# ESP32_layout.net
KiCad netlist of a schematic drawn in EasyEDA
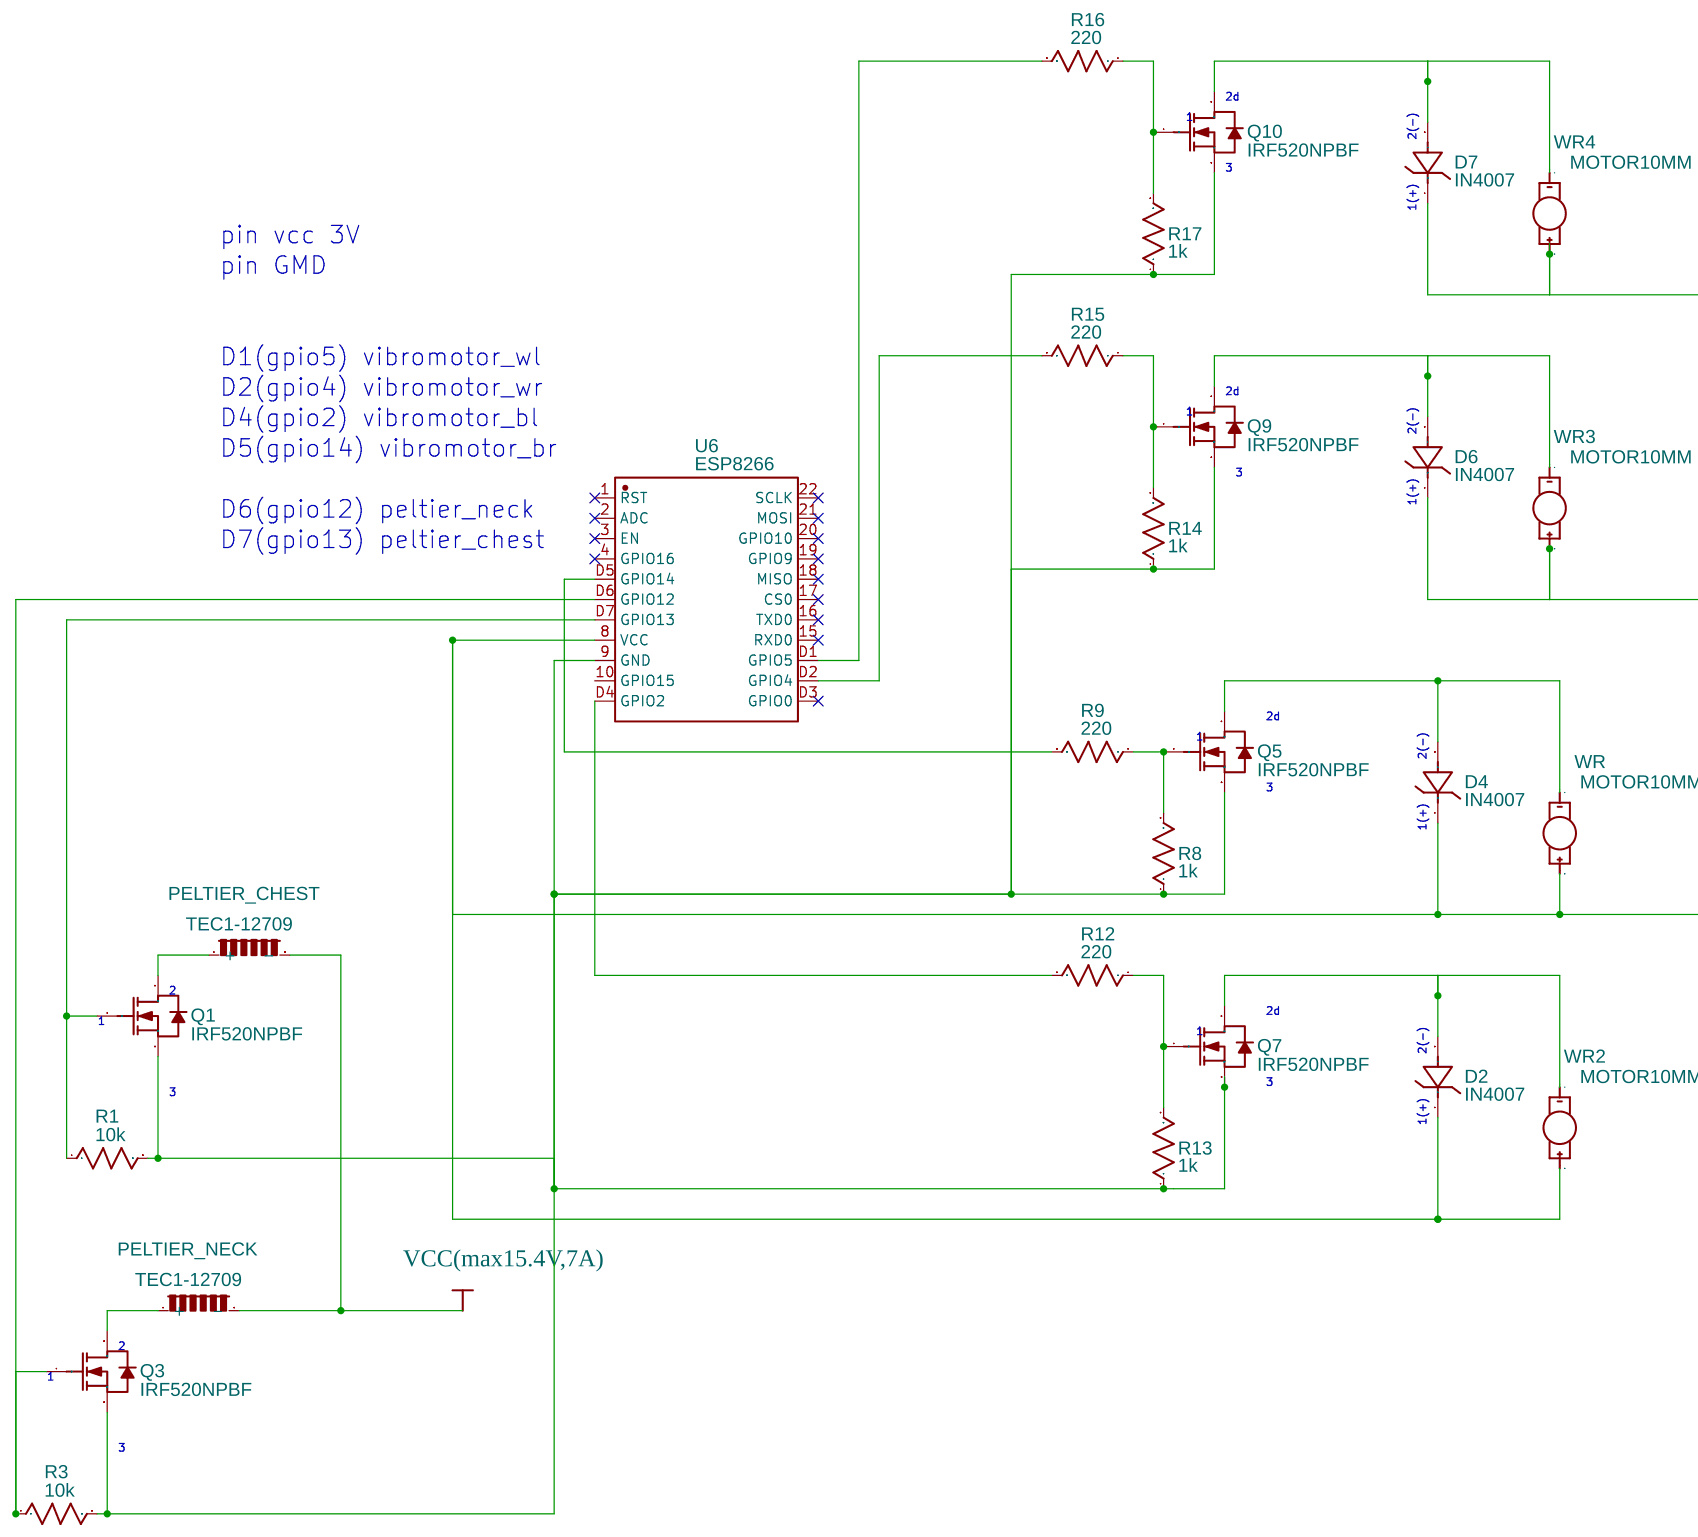
[diagram p0: schema_proto2]
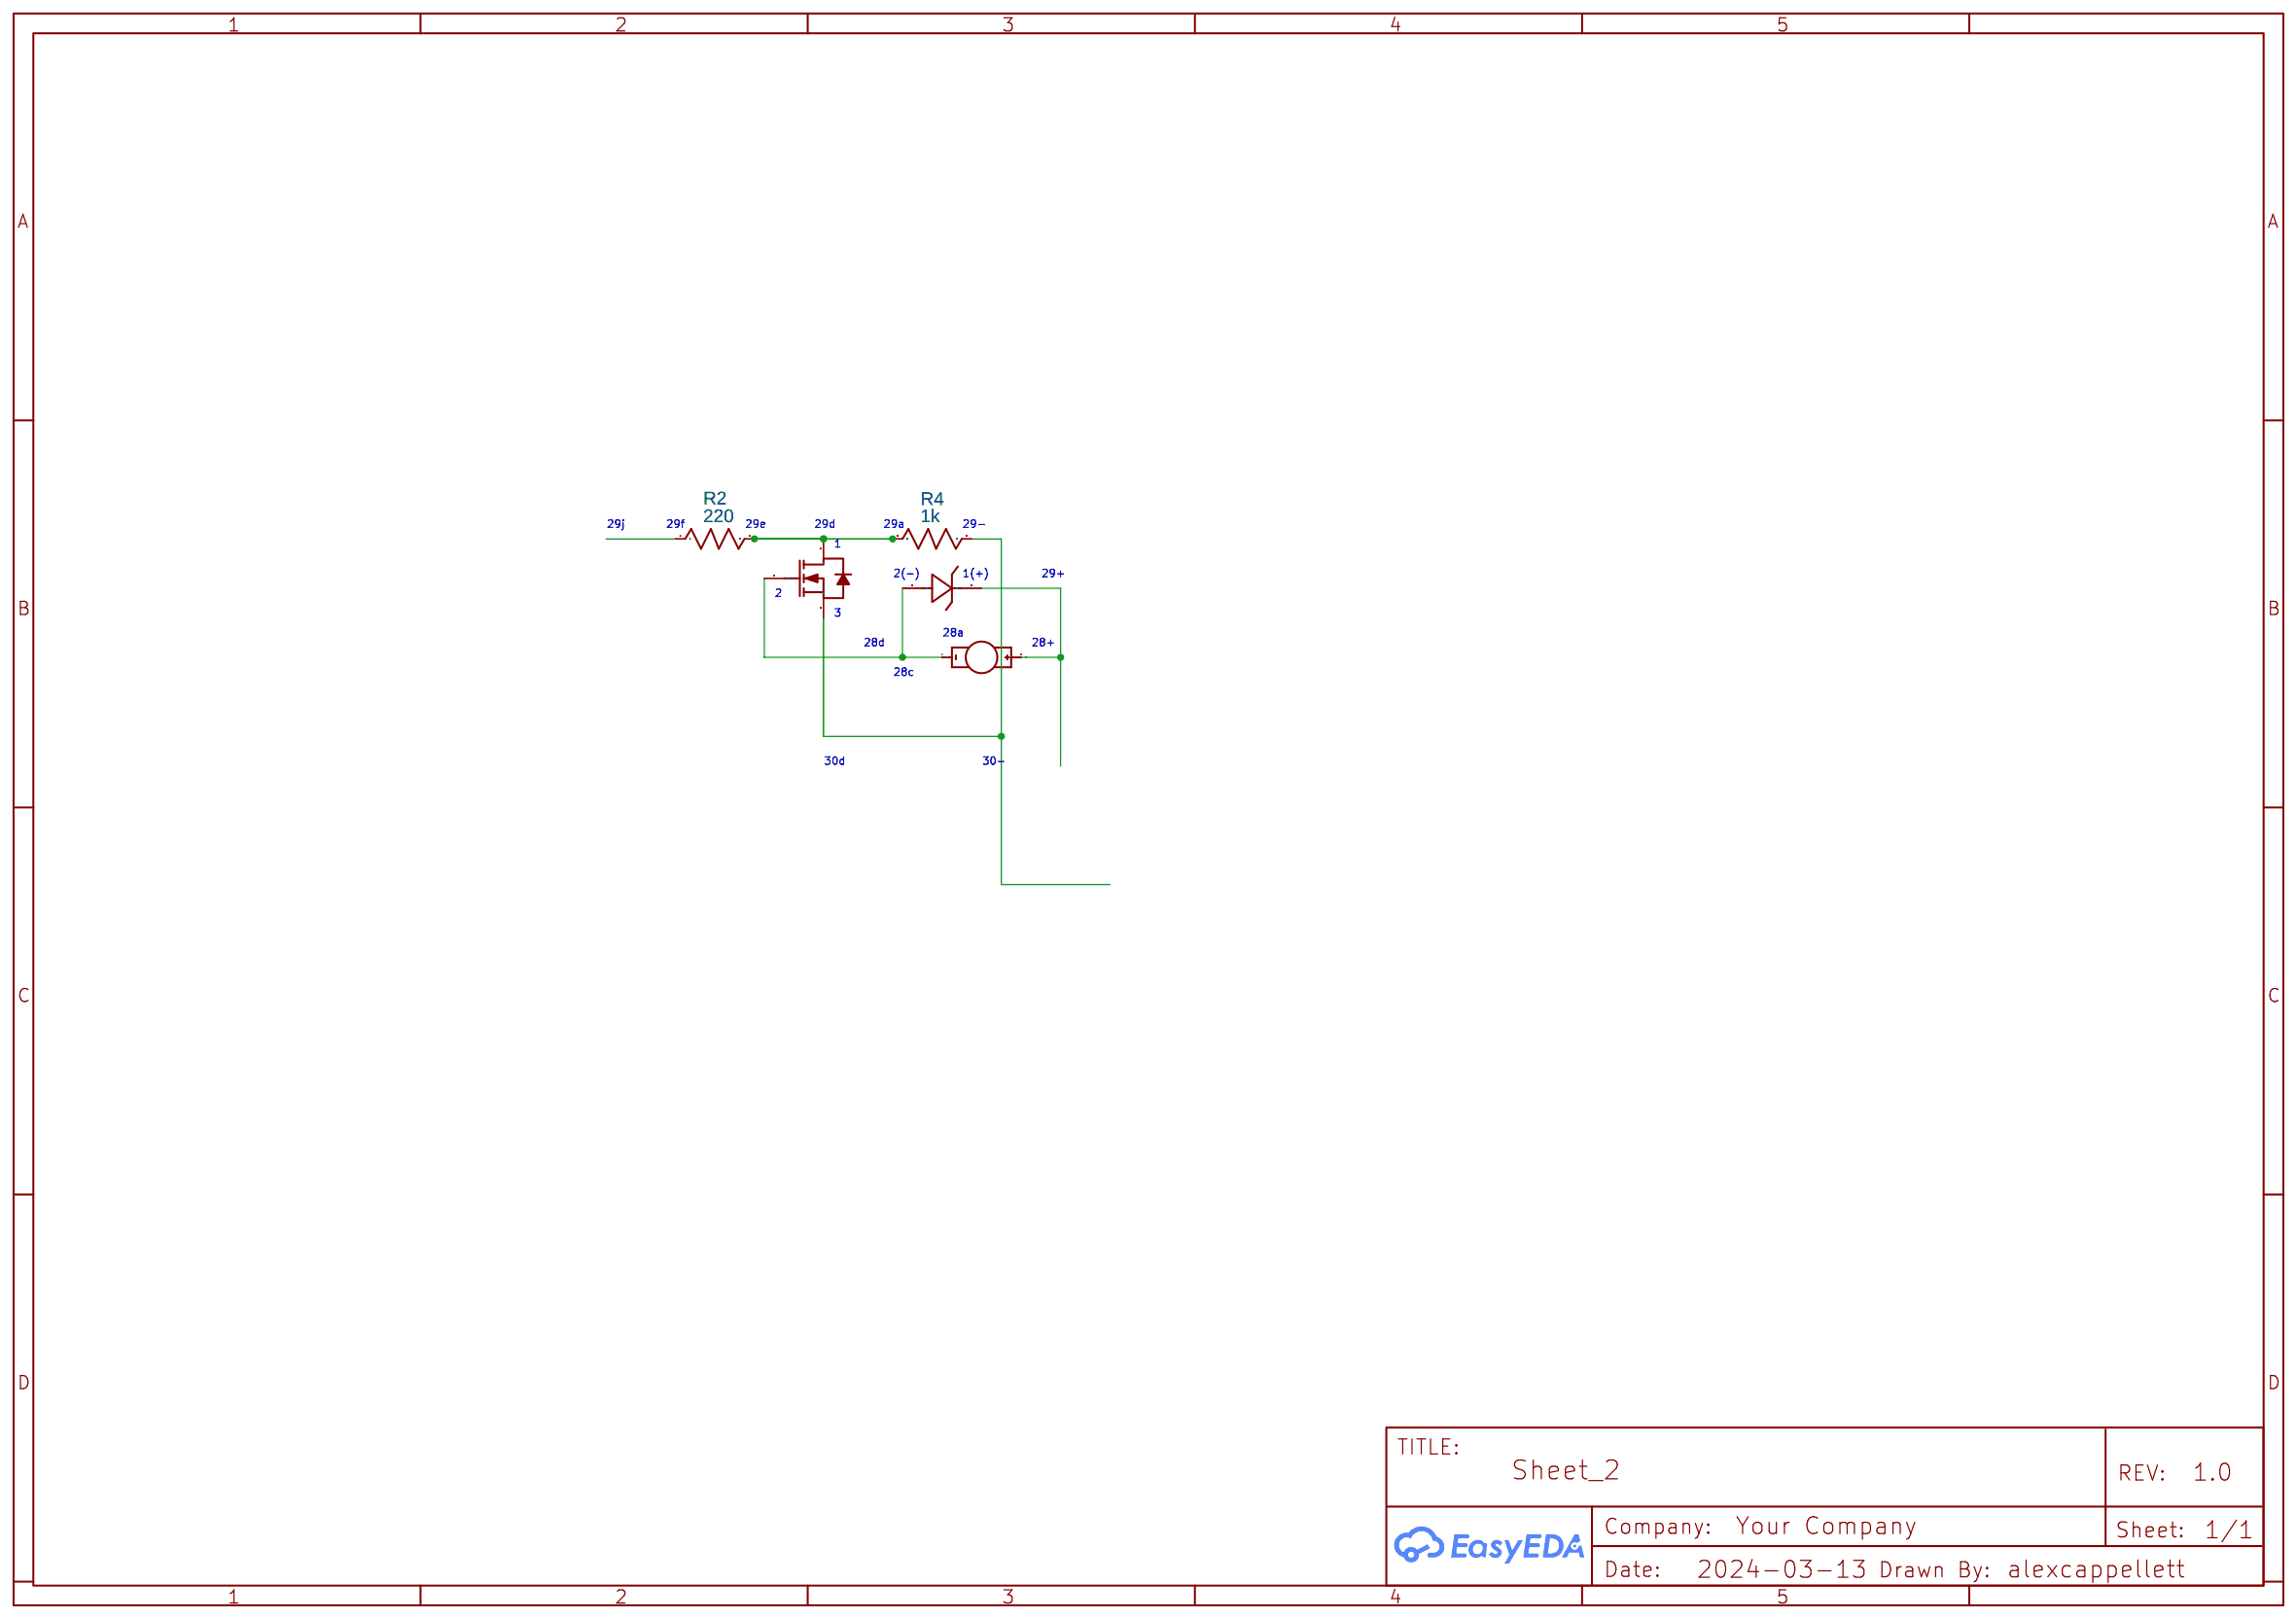
[diagram p1: schema_motor_details]
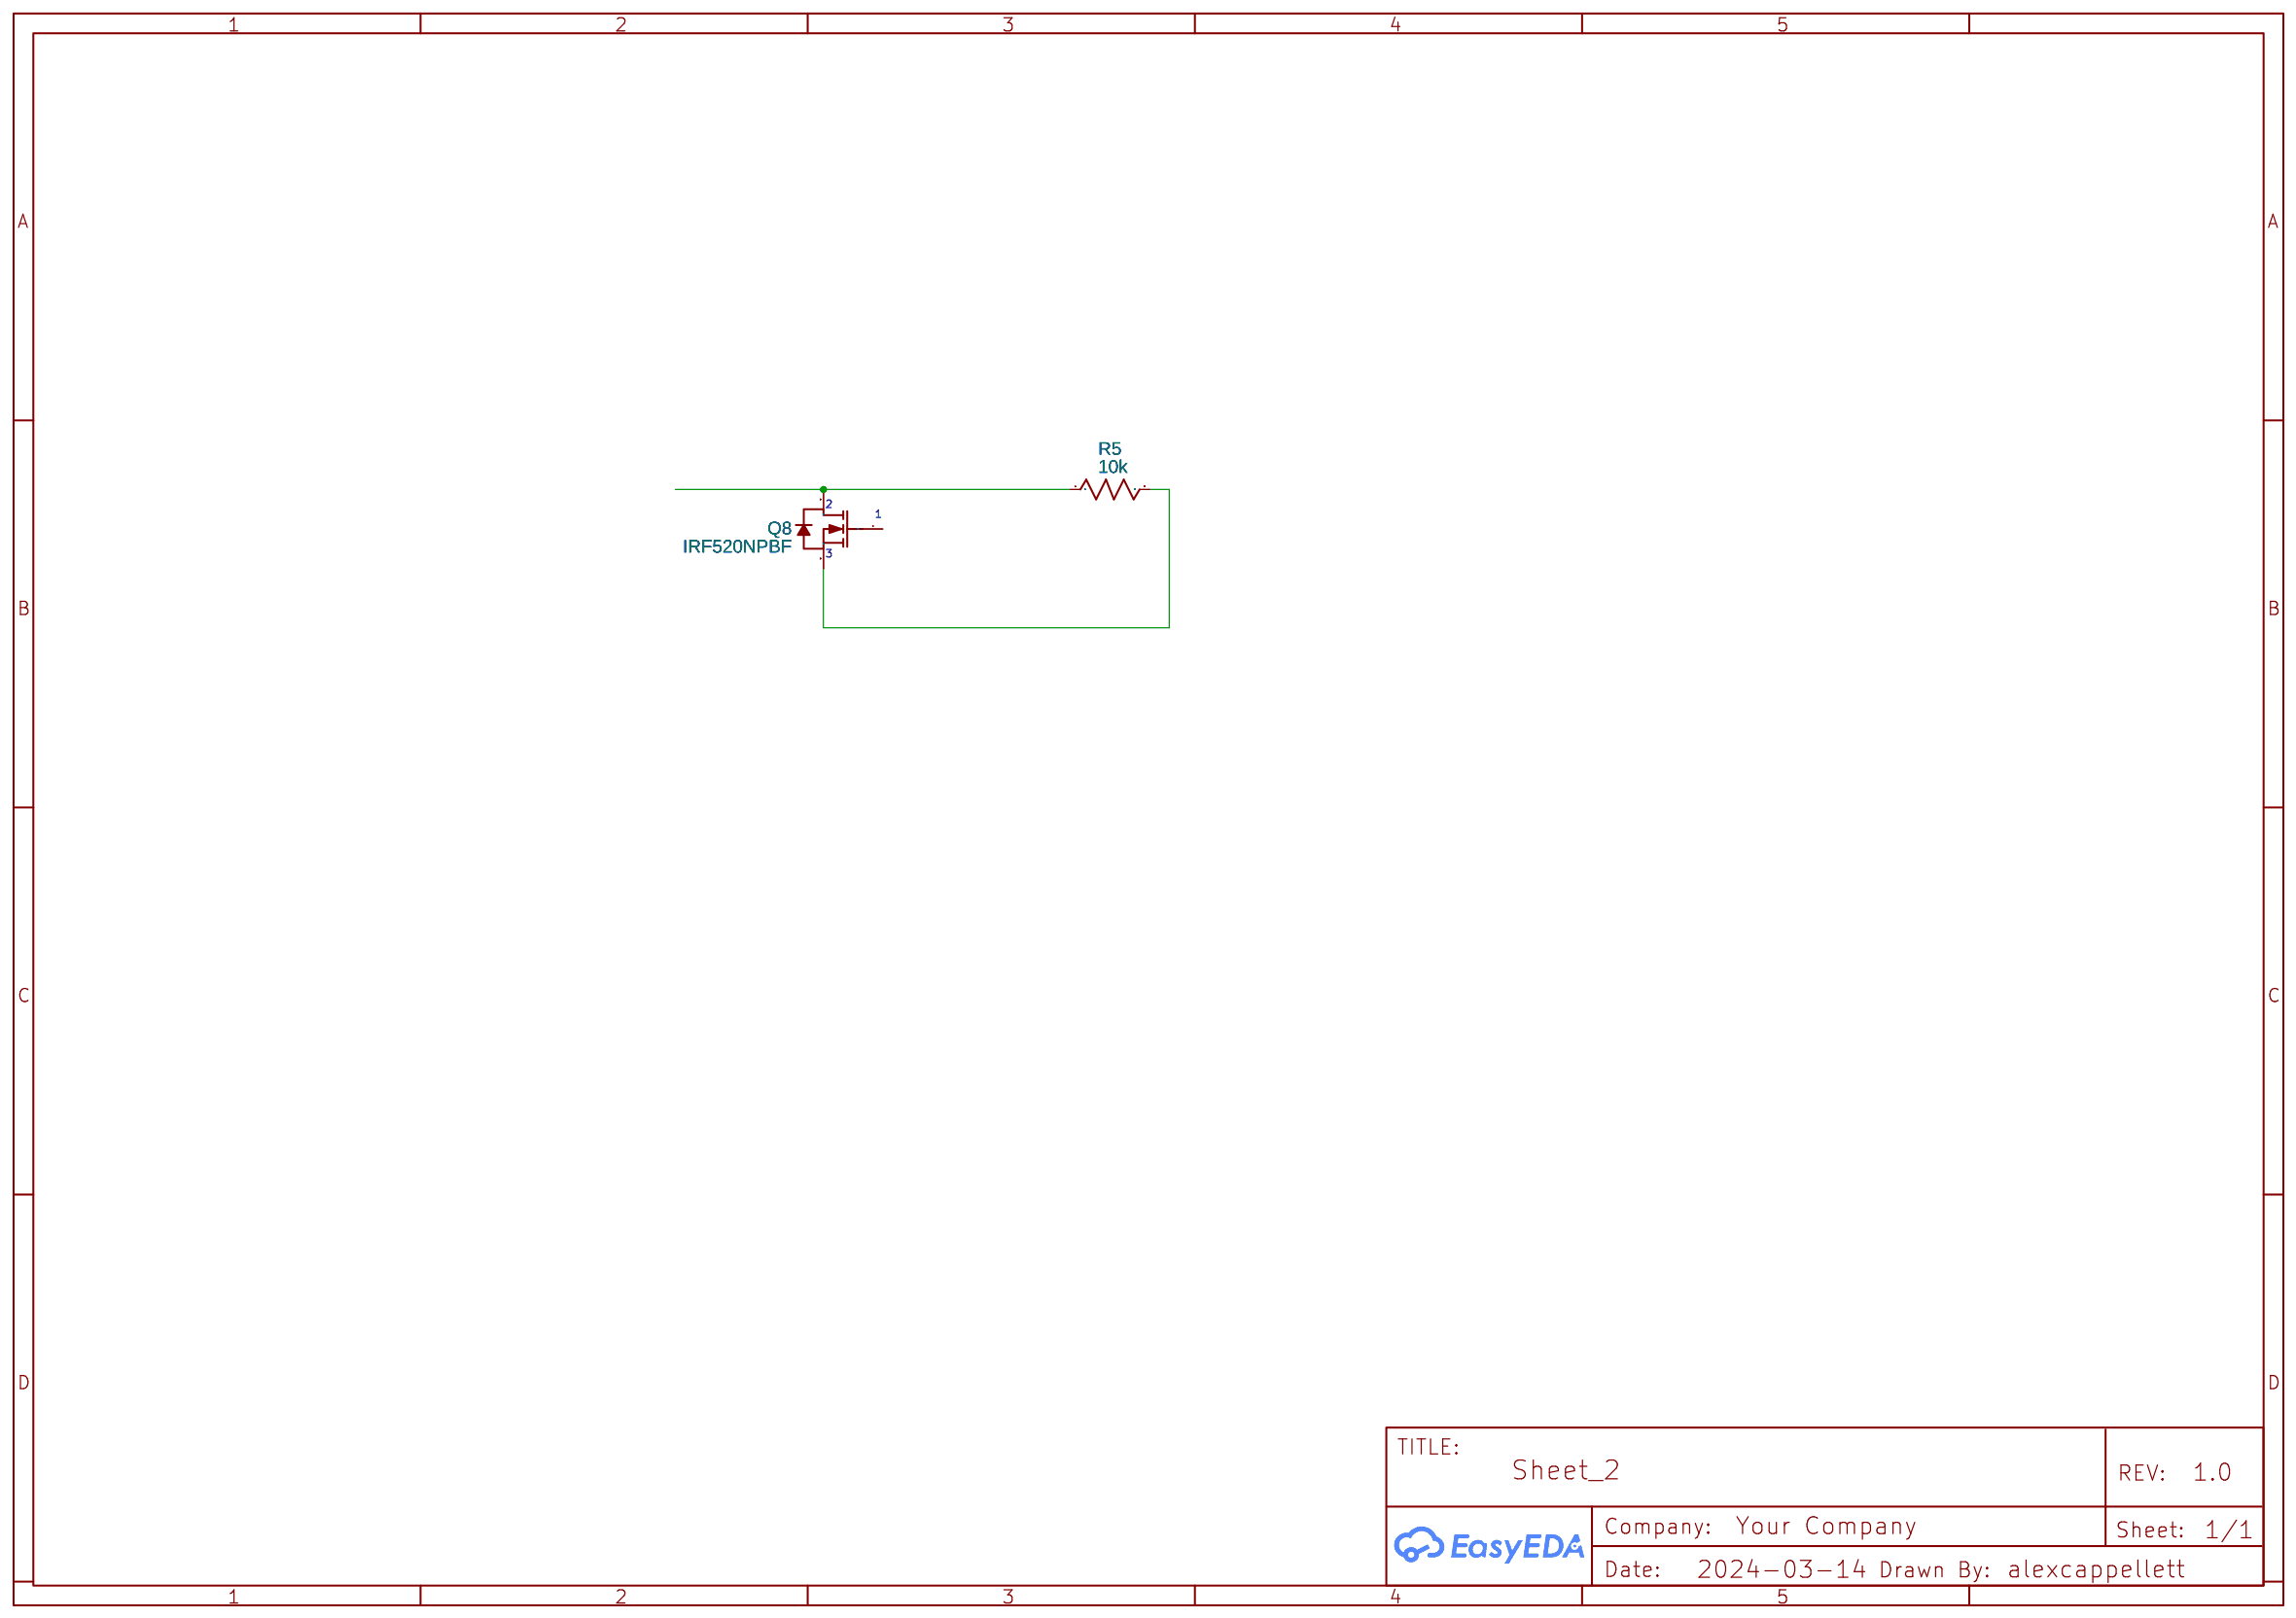
[diagram p2: Sheet_2]

(export (version "E")
  (design (tool "Eeschema 10.0.6"))
  (components
    (comp (ref "D2") (value "IN4007") (libsource (lib "") (part "IN4007")))
    (comp (ref "D4") (value "IN4007") (libsource (lib "") (part "IN4007")))
    (comp (ref "D6") (value "IN4007") (libsource (lib "") (part "IN4007")))
    (comp (ref "D7") (value "IN4007") (libsource (lib "") (part "IN4007")))
    (comp (ref "PELTIER_CHEST") (value "TEC1-12709") (libsource (lib "") (part "Peltier_Element_1")))
    (comp (ref "PELTIER_NECK") (value "TEC1-12709") (libsource (lib "") (part "Peltier_Element")))
    (comp (ref "Q1")
      (value "IRF520NPBF")
      (fields (field (name "Manufacturer") "Infineon(英飞凌)"))
      (libsource (lib "") (part "IRF520NPBF"))
    )
    (comp (ref "Q3")
      (value "IRF520NPBF")
      (fields (field (name "Manufacturer") "Infineon(英飞凌)"))
      (libsource (lib "") (part "IRF520NPBF"))
    )
    (comp (ref "Q5")
      (value "IRF520NPBF")
      (fields (field (name "Manufacturer") "Infineon(英飞凌)"))
      (libsource (lib "") (part "IRF520NPBF"))
    )
    (comp (ref "Q7")
      (value "IRF520NPBF")
      (fields (field (name "Manufacturer") "Infineon(英飞凌)"))
      (libsource (lib "") (part "IRF520NPBF"))
    )
    (comp (ref "Q9")
      (value "IRF520NPBF")
      (fields (field (name "Manufacturer") "Infineon(英飞凌)"))
      (libsource (lib "") (part "IRF520NPBF"))
    )
    (comp (ref "Q10")
      (value "IRF520NPBF")
      (fields (field (name "Manufacturer") "Infineon(英飞凌)"))
      (libsource (lib "") (part "IRF520NPBF"))
    )
    (comp (ref "R1") (value "10k") (libsource (lib "") (part "R_0603_US_1")))
    (comp (ref "R3") (value "10k") (libsource (lib "") (part "R_0603_US_1")))
    (comp (ref "R8") (value "1k") (libsource (lib "") (part "R_0603_US")))
    (comp (ref "R9") (value "220") (libsource (lib "") (part "R_0603_US_2")))
    (comp (ref "R12") (value "220") (libsource (lib "") (part "R_0603_US_2")))
    (comp (ref "R13") (value "1k") (libsource (lib "") (part "R_0603_US")))
    (comp (ref "R14") (value "1k") (libsource (lib "") (part "R_0603_US")))
    (comp (ref "R15") (value "220") (libsource (lib "") (part "R_0603_US_2")))
    (comp (ref "R16") (value "220") (libsource (lib "") (part "R_0603_US_2")))
    (comp (ref "R17") (value "1k") (libsource (lib "") (part "R_0603_US")))
    (comp (ref "U6") (value "ESP8266") (libsource (lib "") (part "ESP8266")))
    (comp (ref "WR") (value "MOTOR10MM") (libsource (lib "") (part "MOTOR10MM")))
    (comp (ref "WR2") (value "MOTOR10MM") (libsource (lib "") (part "MOTOR10MM")))
    (comp (ref "WR3") (value "MOTOR10MM") (libsource (lib "") (part "MOTOR10MM")))
    (comp (ref "WR4") (value "MOTOR10MM") (libsource (lib "") (part "MOTOR10MM")))
    (comp (ref "D1") (value "IN4007") (libsource (lib "") (part "IN4007")))
    (comp (ref "Q2")
      (value "IRF520NPBF")
      (fields (field (name "Manufacturer") "Infineon(英飞凌)"))
      (libsource (lib "") (part "IRF520NPBF"))
    )
    (comp (ref "R2") (value "220") (libsource (lib "") (part "R_0603_US")))
    (comp (ref "R4") (value "1k") (libsource (lib "") (part "R_0603_US")))
    (comp (ref "WR1") (value "MOTOR10MM") (libsource (lib "") (part "MOTOR10MM")))
    (comp (ref "Q8")
      (value "IRF520NPBF")
      (fields (field (name "Manufacturer") "Infineon(英飞凌)"))
      (libsource (lib "") (part "IRF520NPBF"))
    )
    (comp (ref "R5") (value "10k") (libsource (lib "") (part "R_0603_US")))
  )
  (nets
    (net (code "1") (name "Net-(D1-A)") (class "Default")
      (node (ref "D1") (pin "2") (pinfunction "A_2") (pintype "unspecified"))
      (node (ref "Q2") (pin "1") (pinfunction "G_1") (pintype "unspecified"))
      (node (ref "WR1") (pin "-") (pinfunction "-_-") (pintype "unspecified"))
    )
    (net (code "2") (name "Net-(D1-C)") (class "Default")
      (node (ref "D1") (pin "1") (pinfunction "C_1") (pintype "unspecified"))
      (node (ref "WR1") (pin "+") (pinfunction "+_+") (pintype "unspecified"))
    )
    (net (code "3") (name "Net-(D2-A)") (class "Default")
      (node (ref "D2") (pin "2") (pinfunction "A_2") (pintype "unspecified"))
      (node (ref "Q7") (pin "2") (pinfunction "D_2") (pintype "unspecified"))
      (node (ref "WR2") (pin "-") (pinfunction "-_-") (pintype "unspecified"))
    )
    (net (code "4") (name "Net-(D2-C)") (class "Default")
      (node (ref "D2") (pin "1") (pinfunction "C_1") (pintype "unspecified"))
      (node (ref "D4") (pin "1") (pinfunction "C_1") (pintype "unspecified"))
      (node (ref "D6") (pin "1") (pinfunction "C_1") (pintype "unspecified"))
      (node (ref "D7") (pin "1") (pinfunction "C_1") (pintype "unspecified"))
      (node (ref "U6") (pin "8") (pinfunction "VCC_8") (pintype "unspecified"))
      (node (ref "WR") (pin "+") (pinfunction "+_+") (pintype "unspecified"))
      (node (ref "WR2") (pin "+") (pinfunction "+_+") (pintype "unspecified"))
      (node (ref "WR3") (pin "+") (pinfunction "+_+") (pintype "unspecified"))
      (node (ref "WR4") (pin "+") (pinfunction "+_+") (pintype "unspecified"))
    )
    (net (code "5") (name "Net-(D4-A)") (class "Default")
      (node (ref "D4") (pin "2") (pinfunction "A_2") (pintype "unspecified"))
      (node (ref "Q5") (pin "2") (pinfunction "D_2") (pintype "unspecified"))
      (node (ref "WR") (pin "-") (pinfunction "-_-") (pintype "unspecified"))
    )
    (net (code "6") (name "Net-(D6-A)") (class "Default")
      (node (ref "D6") (pin "2") (pinfunction "A_2") (pintype "unspecified"))
      (node (ref "Q9") (pin "2") (pinfunction "D_2") (pintype "unspecified"))
      (node (ref "WR3") (pin "-") (pinfunction "-_-") (pintype "unspecified"))
    )
    (net (code "7") (name "Net-(D7-A)") (class "Default")
      (node (ref "D7") (pin "2") (pinfunction "A_2") (pintype "unspecified"))
      (node (ref "Q10") (pin "2") (pinfunction "D_2") (pintype "unspecified"))
      (node (ref "WR4") (pin "-") (pinfunction "-_-") (pintype "unspecified"))
    )
    (net (code "8") (name "Net-(PELTIER_CHEST-+)") (class "Default")
      (node (ref "PELTIER_CHEST") (pin "1") (pinfunction "+_1") (pintype "unspecified"))
      (node (ref "Q1") (pin "2") (pinfunction "D_2") (pintype "unspecified"))
    )
    (net (code "9") (name "Net-(PELTIER_NECK-+)") (class "Default")
      (node (ref "PELTIER_NECK") (pin "1") (pinfunction "+_1") (pintype "unspecified"))
      (node (ref "Q3") (pin "2") (pinfunction "D_2") (pintype "unspecified"))
    )
    (net (code "10") (name "Net-(Q1-G)") (class "Default")
      (node (ref "Q1") (pin "1") (pinfunction "G_1") (pintype "unspecified"))
      (node (ref "R1") (pin "1") (pinfunction "1_1") (pintype "unspecified"))
      (node (ref "U6") (pin "D7") (pinfunction "GPIO13_D7") (pintype "unspecified"))
    )
    (net (code "11") (name "Net-(Q1-S)") (class "Default")
      (node (ref "Q1") (pin "3") (pinfunction "S_3") (pintype "unspecified"))
      (node (ref "Q10") (pin "3") (pinfunction "S_3") (pintype "unspecified"))
      (node (ref "Q3") (pin "3") (pinfunction "S_3") (pintype "unspecified"))
      (node (ref "Q5") (pin "3") (pinfunction "S_3") (pintype "unspecified"))
      (node (ref "Q7") (pin "3") (pinfunction "S_3") (pintype "unspecified"))
      (node (ref "Q9") (pin "3") (pinfunction "S_3") (pintype "unspecified"))
      (node (ref "R1") (pin "2") (pinfunction "2_2") (pintype "unspecified"))
      (node (ref "R13") (pin "1") (pinfunction "1_1") (pintype "unspecified"))
      (node (ref "R14") (pin "1") (pinfunction "1_1") (pintype "unspecified"))
      (node (ref "R17") (pin "1") (pinfunction "1_1") (pintype "unspecified"))
      (node (ref "R3") (pin "2") (pinfunction "2_2") (pintype "unspecified"))
      (node (ref "R8") (pin "1") (pinfunction "1_1") (pintype "unspecified"))
      (node (ref "U6") (pin "9") (pinfunction "GND_9") (pintype "unspecified"))
    )
    (net (code "12") (name "Net-(Q2-D)") (class "Default")
      (node (ref "Q2") (pin "2") (pinfunction "D_2") (pintype "unspecified"))
      (node (ref "R2") (pin "2") (pinfunction "2_2") (pintype "unspecified"))
      (node (ref "R4") (pin "1") (pinfunction "1_1") (pintype "unspecified"))
    )
    (net (code "13") (name "Net-(Q2-S)") (class "Default")
      (node (ref "Q2") (pin "3") (pinfunction "S_3") (pintype "unspecified"))
      (node (ref "R4") (pin "2") (pinfunction "2_2") (pintype "unspecified"))
    )
    (net (code "14") (name "Net-(Q3-G)") (class "Default")
      (node (ref "Q3") (pin "1") (pinfunction "G_1") (pintype "unspecified"))
      (node (ref "R3") (pin "1") (pinfunction "1_1") (pintype "unspecified"))
      (node (ref "U6") (pin "D6") (pinfunction "GPIO12_D6") (pintype "unspecified"))
    )
    (net (code "15") (name "Net-(Q5-G)") (class "Default")
      (node (ref "Q5") (pin "1") (pinfunction "G_1") (pintype "unspecified"))
      (node (ref "R8") (pin "2") (pinfunction "2_2") (pintype "unspecified"))
      (node (ref "R9") (pin "1") (pinfunction "1_1") (pintype "unspecified"))
    )
    (net (code "16") (name "Net-(Q7-G)") (class "Default")
      (node (ref "Q7") (pin "1") (pinfunction "G_1") (pintype "unspecified"))
      (node (ref "R12") (pin "1") (pinfunction "1_1") (pintype "unspecified"))
      (node (ref "R13") (pin "2") (pinfunction "2_2") (pintype "unspecified"))
    )
    (net (code "17") (name "Net-(Q8-D)") (class "Default")
      (node (ref "Q8") (pin "2") (pinfunction "D_2") (pintype "unspecified"))
      (node (ref "R5") (pin "1") (pinfunction "1_1") (pintype "unspecified"))
    )
    (net (code "18") (name "Net-(Q8-S)") (class "Default")
      (node (ref "Q8") (pin "3") (pinfunction "S_3") (pintype "unspecified"))
      (node (ref "R5") (pin "2") (pinfunction "2_2") (pintype "unspecified"))
    )
    (net (code "19") (name "Net-(Q9-G)") (class "Default")
      (node (ref "Q9") (pin "1") (pinfunction "G_1") (pintype "unspecified"))
      (node (ref "R14") (pin "2") (pinfunction "2_2") (pintype "unspecified"))
      (node (ref "R15") (pin "1") (pinfunction "1_1") (pintype "unspecified"))
    )
    (net (code "20") (name "Net-(Q10-G)") (class "Default")
      (node (ref "Q10") (pin "1") (pinfunction "G_1") (pintype "unspecified"))
      (node (ref "R16") (pin "1") (pinfunction "1_1") (pintype "unspecified"))
      (node (ref "R17") (pin "2") (pinfunction "2_2") (pintype "unspecified"))
    )
    (net (code "21") (name "Net-(U6-GPIO2)") (class "Default")
      (node (ref "R12") (pin "2") (pinfunction "2_2") (pintype "unspecified"))
      (node (ref "U6") (pin "D4") (pinfunction "GPIO2_D4") (pintype "unspecified"))
    )
    (net (code "22") (name "Net-(U6-GPIO4)") (class "Default")
      (node (ref "R15") (pin "2") (pinfunction "2_2") (pintype "unspecified"))
      (node (ref "U6") (pin "D2") (pinfunction "GPIO4_D2") (pintype "unspecified"))
    )
    (net (code "23") (name "Net-(U6-GPIO5)") (class "Default")
      (node (ref "R16") (pin "2") (pinfunction "2_2") (pintype "unspecified"))
      (node (ref "U6") (pin "D1") (pinfunction "GPIO5_D1") (pintype "unspecified"))
    )
    (net (code "24") (name "Net-(U6-GPIO14)") (class "Default")
      (node (ref "R9") (pin "2") (pinfunction "2_2") (pintype "unspecified"))
      (node (ref "U6") (pin "D5") (pinfunction "GPIO14_D5") (pintype "unspecified"))
    )
    (net (code "25") (name "VCC(max15.4V,7A)") (class "Default")
      (node (ref "PELTIER_CHEST") (pin "2") (pinfunction "-_2") (pintype "unspecified"))
      (node (ref "PELTIER_NECK") (pin "2") (pinfunction "-_2") (pintype "unspecified"))
    )
    (net (code "26") (name "unconnected-(Q8-G-Pad1)") (class "Default")
      (node (ref "Q8") (pin "1") (pinfunction "G_1") (pintype "unspecified"))
    )
    (net (code "27") (name "unconnected-(R2-Pad1)") (class "Default")
      (node (ref "R2") (pin "1") (pinfunction "1_1") (pintype "unspecified"))
    )
    (net (code "28") (name "unconnected-(U6-ADC-Pad2)") (class "Default")
      (node (ref "U6") (pin "2") (pinfunction "ADC_2") (pintype "unspecified+no_connect"))
    )
    (net (code "29") (name "unconnected-(U6-CS0-Pad17)") (class "Default")
      (node (ref "U6") (pin "17") (pinfunction "CS0_17") (pintype "unspecified+no_connect"))
    )
    (net (code "30") (name "unconnected-(U6-EN-Pad3)") (class "Default")
      (node (ref "U6") (pin "3") (pinfunction "EN_3") (pintype "unspecified+no_connect"))
    )
    (net (code "31") (name "unconnected-(U6-GPIO0-PadD3)") (class "Default")
      (node (ref "U6") (pin "D3") (pinfunction "GPIO0_D3") (pintype "unspecified+no_connect"))
    )
    (net (code "32") (name "unconnected-(U6-GPIO9-Pad19)") (class "Default")
      (node (ref "U6") (pin "19") (pinfunction "GPIO9_19") (pintype "unspecified+no_connect"))
    )
    (net (code "33") (name "unconnected-(U6-GPIO10-Pad20)") (class "Default")
      (node (ref "U6") (pin "20") (pinfunction "GPIO10_20") (pintype "unspecified+no_connect"))
    )
    (net (code "34") (name "unconnected-(U6-GPIO15-Pad10)") (class "Default")
      (node (ref "U6") (pin "10") (pinfunction "GPIO15_10") (pintype "unspecified"))
    )
    (net (code "35") (name "unconnected-(U6-GPIO16-Pad4)") (class "Default")
      (node (ref "U6") (pin "4") (pinfunction "GPIO16_4") (pintype "unspecified+no_connect"))
    )
    (net (code "36") (name "unconnected-(U6-MISO-Pad18)") (class "Default")
      (node (ref "U6") (pin "18") (pinfunction "MISO_18") (pintype "unspecified+no_connect"))
    )
    (net (code "37") (name "unconnected-(U6-MOSI-Pad21)") (class "Default")
      (node (ref "U6") (pin "21") (pinfunction "MOSI_21") (pintype "unspecified+no_connect"))
    )
    (net (code "38") (name "unconnected-(U6-RST-Pad1)") (class "Default")
      (node (ref "U6") (pin "1") (pinfunction "RST_1") (pintype "unspecified+no_connect"))
    )
    (net (code "39") (name "unconnected-(U6-RXD0-Pad15)") (class "Default")
      (node (ref "U6") (pin "15") (pinfunction "RXD0_15") (pintype "unspecified+no_connect"))
    )
    (net (code "40") (name "unconnected-(U6-SCLK-Pad22)") (class "Default")
      (node (ref "U6") (pin "22") (pinfunction "SCLK_22") (pintype "unspecified+no_connect"))
    )
    (net (code "41") (name "unconnected-(U6-TXD0-Pad16)") (class "Default")
      (node (ref "U6") (pin "16") (pinfunction "TXD0_16") (pintype "unspecified+no_connect"))
    )
  )
)
